# eth_conn1.net
KiCad netlist of a schematic drawn in EAGLE
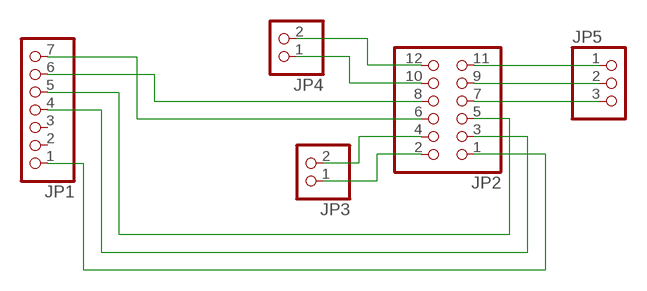
[diagram p0: schematic, sheet 1]

(export (version "E")
  (design (tool "Eeschema 10.0.6"))
  (components
    (comp (ref "JP1")
      (value "PINHD-1X7")
      (footprint "eagle-import:1X07")
      (libsource (lib "eagle-import") (part "PINHD-1X7"))
    )
    (comp (ref "JP2")
      (value "PINHD-2X6")
      (footprint "eagle-import:2X06")
      (libsource (lib "eagle-import") (part "PINHD-2X6"))
    )
    (comp (ref "JP3")
      (value "PINHD-1X2")
      (footprint "eagle-import:1X02")
      (libsource (lib "eagle-import") (part "PINHD-1X2"))
    )
    (comp (ref "JP4")
      (value "PINHD-1X2")
      (footprint "eagle-import:1X02")
      (libsource (lib "eagle-import") (part "PINHD-1X2"))
    )
    (comp (ref "JP5")
      (value "PINHD-1X3")
      (footprint "eagle-import:1X03")
      (libsource (lib "eagle-import") (part "PINHD-1X3"))
    )
  )
  (nets
    (net (code "1") (name "Net-(JP1-Pad1)") (class "Default")
      (node (ref "JP1") (pin "1") (pinfunction "1_1") (pintype "passive"))
      (node (ref "JP2") (pin "1") (pinfunction "1_1") (pintype "passive"))
    )
    (net (code "2") (name "Net-(JP1-Pad4)") (class "Default")
      (node (ref "JP1") (pin "4") (pinfunction "4_4") (pintype "passive"))
      (node (ref "JP2") (pin "3") (pinfunction "3_3") (pintype "passive"))
    )
    (net (code "3") (name "Net-(JP1-Pad5)") (class "Default")
      (node (ref "JP1") (pin "5") (pinfunction "5_5") (pintype "passive"))
      (node (ref "JP2") (pin "5") (pinfunction "5_5") (pintype "passive"))
    )
    (net (code "4") (name "Net-(JP1-Pad6)") (class "Default")
      (node (ref "JP1") (pin "6") (pinfunction "6_6") (pintype "passive"))
      (node (ref "JP2") (pin "8") (pinfunction "8_8") (pintype "passive"))
    )
    (net (code "5") (name "Net-(JP1-Pad7)") (class "Default")
      (node (ref "JP1") (pin "7") (pinfunction "7_7") (pintype "passive"))
      (node (ref "JP2") (pin "6") (pinfunction "6_6") (pintype "passive"))
    )
    (net (code "6") (name "Net-(JP2-Pad2)") (class "Default")
      (node (ref "JP2") (pin "2") (pinfunction "2_2") (pintype "passive"))
      (node (ref "JP3") (pin "1") (pinfunction "1_1") (pintype "passive"))
    )
    (net (code "7") (name "Net-(JP2-Pad4)") (class "Default")
      (node (ref "JP2") (pin "4") (pinfunction "4_4") (pintype "passive"))
      (node (ref "JP3") (pin "2") (pinfunction "2_2") (pintype "passive"))
    )
    (net (code "8") (name "Net-(JP2-Pad7)") (class "Default")
      (node (ref "JP2") (pin "7") (pinfunction "7_7") (pintype "passive"))
      (node (ref "JP5") (pin "3") (pinfunction "3_3") (pintype "passive"))
    )
    (net (code "9") (name "Net-(JP2-Pad9)") (class "Default")
      (node (ref "JP2") (pin "9") (pinfunction "9_9") (pintype "passive"))
      (node (ref "JP5") (pin "2") (pinfunction "2_2") (pintype "passive"))
    )
    (net (code "10") (name "Net-(JP2-Pad10)") (class "Default")
      (node (ref "JP2") (pin "10") (pinfunction "10_10") (pintype "passive"))
      (node (ref "JP4") (pin "1") (pinfunction "1_1") (pintype "passive"))
    )
    (net (code "11") (name "Net-(JP2-Pad11)") (class "Default")
      (node (ref "JP2") (pin "11") (pinfunction "11_11") (pintype "passive"))
      (node (ref "JP5") (pin "1") (pinfunction "1_1") (pintype "passive"))
    )
    (net (code "12") (name "Net-(JP2-Pad12)") (class "Default")
      (node (ref "JP2") (pin "12") (pinfunction "12_12") (pintype "passive"))
      (node (ref "JP4") (pin "2") (pinfunction "2_2") (pintype "passive"))
    )
    (net (code "13") (name "unconnected-(JP1-Pad2)") (class "Default")
      (node (ref "JP1") (pin "2") (pinfunction "2_2") (pintype "passive"))
    )
    (net (code "14") (name "unconnected-(JP1-Pad3)") (class "Default")
      (node (ref "JP1") (pin "3") (pinfunction "3_3") (pintype "passive"))
    )
  )
)
